# LED0805-3_Sch.net
KiCad netlist of a schematic drawn in Altium Designer
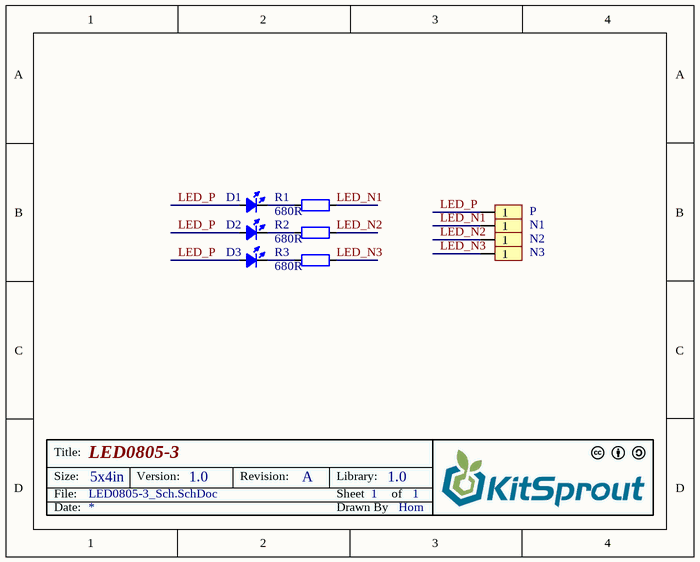
[diagram p0: LED0805-3_Sch.SchDoc]

(export (version "E")
  (design (tool "Eeschema 10.0.6"))
  (components
    (comp (ref "D1")
      (value "LED_0805")
      (footprint "PCB_ActiveLED:LED_0805_BLUE")
      (description "LED")
      (libsource (lib "SCH_Active") (part "LED_0805"))
    )
    (comp (ref "D2")
      (value "LED_0805")
      (footprint "PCB_ActiveLED:LED_0805_BLUE")
      (description "LED")
      (libsource (lib "SCH_Active") (part "LED_0805"))
    )
    (comp (ref "D3")
      (value "LED_0805")
      (footprint "PCB_ActiveLED:LED_0805_BLUE")
      (description "LED")
      (libsource (lib "SCH_Active") (part "LED_0805"))
    )
    (comp (ref "N1")
      (value "HDR-PAD_2.54")
      (footprint "PCB_ConnectorHDR:HDR-PAD_2.54")
      (description "Header")
      (libsource (lib "SCH_ConnectorHDR") (part "HDR-PAD_2.54"))
    )
    (comp (ref "N2")
      (value "HDR-PAD_2.54")
      (footprint "PCB_ConnectorHDR:HDR-PAD_2.54")
      (description "Header")
      (libsource (lib "SCH_ConnectorHDR") (part "HDR-PAD_2.54"))
    )
    (comp (ref "N3")
      (value "HDR-PAD_2.54")
      (footprint "PCB_ConnectorHDR:HDR-PAD_2.54")
      (description "Header")
      (libsource (lib "SCH_ConnectorHDR") (part "HDR-PAD_2.54"))
    )
    (comp (ref "P")
      (value "HDR-PAD_2.54")
      (footprint "PCB_ConnectorHDR:HDR-PAD_2.54")
      (description "Header")
      (libsource (lib "SCH_ConnectorHDR") (part "HDR-PAD_2.54"))
    )
    (comp (ref "R1")
      (value "680R")
      (footprint "PCB_PassiveRes:RES_0805")
      (description "Resistor")
      (fields (field (name "Comment") "Res_0805"))
      (libsource (lib "SCH_Passive") (part "Res_0805"))
    )
    (comp (ref "R2")
      (value "680R")
      (footprint "PCB_PassiveRes:RES_0805")
      (description "Resistor")
      (fields (field (name "Comment") "Res_0805"))
      (libsource (lib "SCH_Passive") (part "Res_0805"))
    )
    (comp (ref "R3")
      (value "680R")
      (footprint "PCB_PassiveRes:RES_0805")
      (description "Resistor")
      (fields (field (name "Comment") "Res_0805"))
      (libsource (lib "SCH_Passive") (part "Res_0805"))
    )
  )
  (nets
    (net (code "1") (name "/LED_N1") (class "Default")
      (node (ref "N1") (pin "1") (pinfunction "1_1") (pintype "passive"))
      (node (ref "R1") (pin "2") (pinfunction "2_2") (pintype "passive"))
    )
    (net (code "2") (name "/LED_N2") (class "Default")
      (node (ref "N2") (pin "1") (pinfunction "1_1") (pintype "passive"))
      (node (ref "R2") (pin "2") (pinfunction "2_2") (pintype "passive"))
    )
    (net (code "3") (name "/LED_N3") (class "Default")
      (node (ref "N3") (pin "1") (pinfunction "1_1") (pintype "passive"))
      (node (ref "R3") (pin "2") (pinfunction "2_2") (pintype "passive"))
    )
    (net (code "4") (name "/LED_P") (class "Default")
      (node (ref "D1") (pin "1") (pinfunction "A_1") (pintype "passive"))
      (node (ref "D2") (pin "1") (pinfunction "A_1") (pintype "passive"))
      (node (ref "D3") (pin "1") (pinfunction "A_1") (pintype "passive"))
      (node (ref "P") (pin "1") (pinfunction "1_1") (pintype "passive"))
    )
    (net (code "5") (name "Net-(D1-K)") (class "Default")
      (node (ref "D1") (pin "2") (pinfunction "K_2") (pintype "passive"))
      (node (ref "R1") (pin "1") (pinfunction "1_1") (pintype "passive"))
    )
    (net (code "6") (name "Net-(D2-K)") (class "Default")
      (node (ref "D2") (pin "2") (pinfunction "K_2") (pintype "passive"))
      (node (ref "R2") (pin "1") (pinfunction "1_1") (pintype "passive"))
    )
    (net (code "7") (name "Net-(D3-K)") (class "Default")
      (node (ref "D3") (pin "2") (pinfunction "K_2") (pintype "passive"))
      (node (ref "R3") (pin "1") (pinfunction "1_1") (pintype "passive"))
    )
  )
)
